# RDA5807FP_I2S_MAX98357A_SETUP.net
KiCad netlist of a schematic drawn in EAGLE
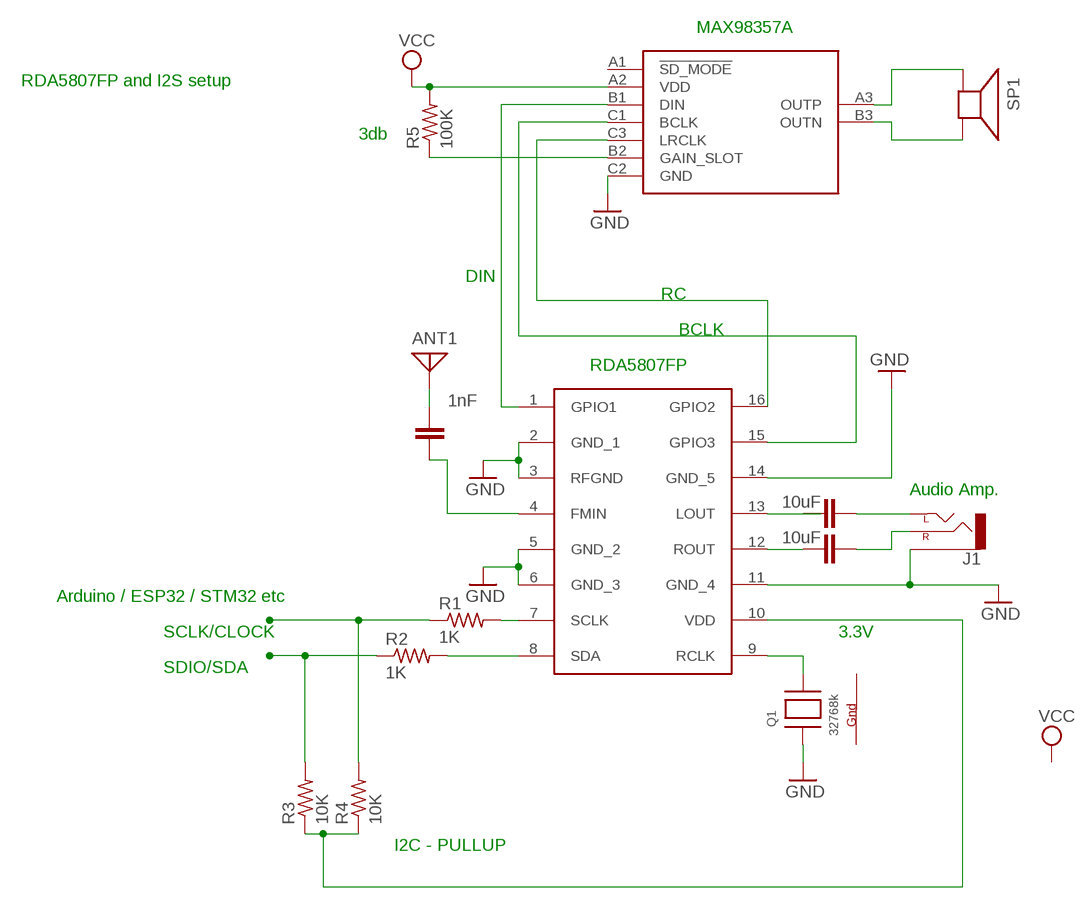
[diagram p0: schematic, sheet 1]

(export (version "E")
  (design (tool "Eeschema 10.0.6"))
  (components
    (comp (ref "ANT1")
      (value "ANTENNA")
      (footprint "eagle-import:PAD-01")
      (libsource (lib "eagle-import") (part "ANTENNA"))
    )
    (comp (ref "J1")
      (value "AUDIO_JACK_2.5MMSPECIAL_POGO_PINS")
      (footprint "eagle-import:STEREOJACK2.5MM_SPECIAL_POGOPINS")
      (libsource (lib "eagle-import") (part "AUDIO_JACK_2.5MMSPECIAL_POGO_PINS"))
    )
    (comp (ref "Q1")
      (value "32768k")
      (footprint "eagle-import:NX3225")
      (libsource (lib "eagle-import") (part "XTAL-4-3225"))
    )
    (comp (ref "R1")
      (value "1K")
      (footprint "eagle-import:0204V")
      (libsource (lib "eagle-import") (part "R-US_0204/2V"))
    )
    (comp (ref "R2")
      (value "1K")
      (footprint "eagle-import:0204V")
      (libsource (lib "eagle-import") (part "R-US_0204/2V"))
    )
    (comp (ref "R3")
      (value "10K")
      (footprint "eagle-import:0204V")
      (libsource (lib "eagle-import") (part "R-US_0204/2V"))
    )
    (comp (ref "R4")
      (value "10K")
      (footprint "eagle-import:0204V")
      (libsource (lib "eagle-import") (part "R-US_0204/2V"))
    )
    (comp (ref "R5")
      (value "100K")
      (footprint "eagle-import:0204V")
      (libsource (lib "eagle-import") (part "R-US_0204/2V"))
    )
    (comp (ref "SP1")
      (value "SPEAKER/PS12")
      (footprint "eagle-import:PS12")
      (libsource (lib "eagle-import") (part "SPEAKER/PS12"))
    )
    (comp (ref "U$1")
      (value "RDA5807FPRDA5807FP")
      (footprint "eagle-import:RDA5807FP")
      (libsource (lib "eagle-import") (part "RDA5807FPRDA5807FP"))
    )
    (comp (ref "U1")
      (value "MAX98357A")
      (footprint "eagle-import:MAX98357A")
      (libsource (lib "eagle-import") (part "MAX98357A"))
    )
  )
  (nets
    (net (code "1") (name "/G1") (class "Default")
      (node (ref "Q1") (pin "4") (pinfunction "G1_4") (pintype "power_in"))
    )
    (net (code "2") (name "/G2") (class "Default")
      (node (ref "Q1") (pin "2") (pinfunction "G2_2") (pintype "power_in"))
    )
    (net (code "3") (name "GND") (class "Default")
      (node (ref "J1") (pin "RING1") (pinfunction "SLEEVE_RING1") (pintype "bidirectional"))
      (node (ref "Q1") (pin "1") (pinfunction "X1_1") (pintype "bidirectional"))
      (node (ref "U$1") (pin "11") (pinfunction "GND_4_11") (pintype "bidirectional"))
      (node (ref "U$1") (pin "14") (pinfunction "GND_5_14") (pintype "bidirectional"))
      (node (ref "U$1") (pin "2") (pinfunction "GND_1_2") (pintype "bidirectional"))
      (node (ref "U$1") (pin "3") (pinfunction "RFGND_3") (pintype "bidirectional"))
      (node (ref "U$1") (pin "5") (pinfunction "GND_2_5") (pintype "bidirectional"))
      (node (ref "U$1") (pin "6") (pinfunction "GND_3_6") (pintype "bidirectional"))
      (node (ref "U1") (pin "C2") (pinfunction "GND_C2") (pintype "bidirectional"))
    )
    (net (code "4") (name "Net-(Q1-X2)") (class "Default")
      (node (ref "Q1") (pin "3") (pinfunction "X2_3") (pintype "bidirectional"))
      (node (ref "U$1") (pin "9") (pinfunction "RCLK_9") (pintype "bidirectional"))
    )
    (net (code "5") (name "Net-(R1-Pad1)") (class "Default")
      (node (ref "R1") (pin "1") (pinfunction "1_1") (pintype "passive"))
      (node (ref "R4") (pin "2") (pinfunction "2_2") (pintype "passive"))
    )
    (net (code "6") (name "Net-(R2-Pad1)") (class "Default")
      (node (ref "R2") (pin "1") (pinfunction "1_1") (pintype "passive"))
      (node (ref "R3") (pin "2") (pinfunction "2_2") (pintype "passive"))
    )
    (net (code "7") (name "Net-(SP1-+)") (class "Default")
      (node (ref "SP1") (pin "P$1") (pinfunction "+_P$1") (pintype "passive"))
      (node (ref "U1") (pin "A3") (pinfunction "OUTP_A3") (pintype "bidirectional"))
    )
    (net (code "8") (name "Net-(SP1--)") (class "Default")
      (node (ref "SP1") (pin "P$2") (pinfunction "-_P$2") (pintype "passive"))
      (node (ref "U1") (pin "B3") (pinfunction "OUTN_B3") (pintype "bidirectional"))
    )
    (net (code "9") (name "Net-(U$1-GPIO1)") (class "Default")
      (node (ref "U$1") (pin "1") (pinfunction "GPIO1_1") (pintype "bidirectional"))
      (node (ref "U1") (pin "B1") (pinfunction "DIN_B1") (pintype "bidirectional"))
    )
    (net (code "10") (name "Net-(U$1-GPIO2)") (class "Default")
      (node (ref "U$1") (pin "16") (pinfunction "GPIO2_16") (pintype "bidirectional"))
      (node (ref "U1") (pin "C3") (pinfunction "LRCLK_C3") (pintype "bidirectional"))
    )
    (net (code "11") (name "Net-(U$1-GPIO3)") (class "Default")
      (node (ref "U$1") (pin "15") (pinfunction "GPIO3_15") (pintype "bidirectional"))
      (node (ref "U1") (pin "C1") (pinfunction "BCLK_C1") (pintype "bidirectional"))
    )
    (net (code "12") (name "Net-(U$1-SCLK)") (class "Default")
      (node (ref "R1") (pin "2") (pinfunction "2_2") (pintype "passive"))
      (node (ref "U$1") (pin "7") (pinfunction "SCLK_7") (pintype "bidirectional"))
    )
    (net (code "13") (name "Net-(U$1-SDA)") (class "Default")
      (node (ref "R2") (pin "2") (pinfunction "2_2") (pintype "passive"))
      (node (ref "U$1") (pin "8") (pinfunction "SDA_8") (pintype "bidirectional"))
    )
    (net (code "14") (name "Net-(U$1-VDD)") (class "Default")
      (node (ref "R3") (pin "1") (pinfunction "1_1") (pintype "passive"))
      (node (ref "R4") (pin "1") (pinfunction "1_1") (pintype "passive"))
      (node (ref "U$1") (pin "10") (pinfunction "VDD_10") (pintype "bidirectional"))
    )
    (net (code "15") (name "Net-(U1-GAIN_SLOT)") (class "Default")
      (node (ref "R5") (pin "1") (pinfunction "1_1") (pintype "passive"))
      (node (ref "U1") (pin "B2") (pinfunction "GAIN_SLOT_B2") (pintype "bidirectional"))
    )
    (net (code "16") (name "VCC") (class "Default")
      (node (ref "R5") (pin "2") (pinfunction "2_2") (pintype "passive"))
      (node (ref "U1") (pin "A2") (pinfunction "VDD_A2") (pintype "bidirectional"))
    )
    (net (code "17") (name "unconnected-(ANT1-Pad1)") (class "Default")
      (node (ref "ANT1") (pin "1") (pinfunction "1_1") (pintype "output"))
    )
    (net (code "18") (name "unconnected-(J1-LEFT-PadSHIELD)") (class "Default")
      (node (ref "J1") (pin "SHIELD") (pinfunction "LEFT_SHIELD") (pintype "bidirectional"))
    )
    (net (code "19") (name "unconnected-(J1-RIGHT-PadTIP)") (class "Default")
      (node (ref "J1") (pin "TIP") (pinfunction "RIGHT_TIP") (pintype "bidirectional"))
    )
    (net (code "20") (name "unconnected-(U$1-FMIN-Pad4)") (class "Default")
      (node (ref "U$1") (pin "4") (pinfunction "FMIN_4") (pintype "bidirectional"))
    )
    (net (code "21") (name "unconnected-(U$1-LOUT-Pad13)") (class "Default")
      (node (ref "U$1") (pin "13") (pinfunction "LOUT_13") (pintype "bidirectional"))
    )
    (net (code "22") (name "unconnected-(U$1-ROUT-Pad12)") (class "Default")
      (node (ref "U$1") (pin "12") (pinfunction "ROUT_12") (pintype "bidirectional"))
    )
    (net (code "23") (name "unconnected-(U1-~{SD_MODE}-PadA1)") (class "Default")
      (node (ref "U1") (pin "A1") (pinfunction "~{SD_MODE}_A1") (pintype "bidirectional"))
    )
  )
)
